# logger3.net
KiCad netlist of a schematic drawn in EAGLE
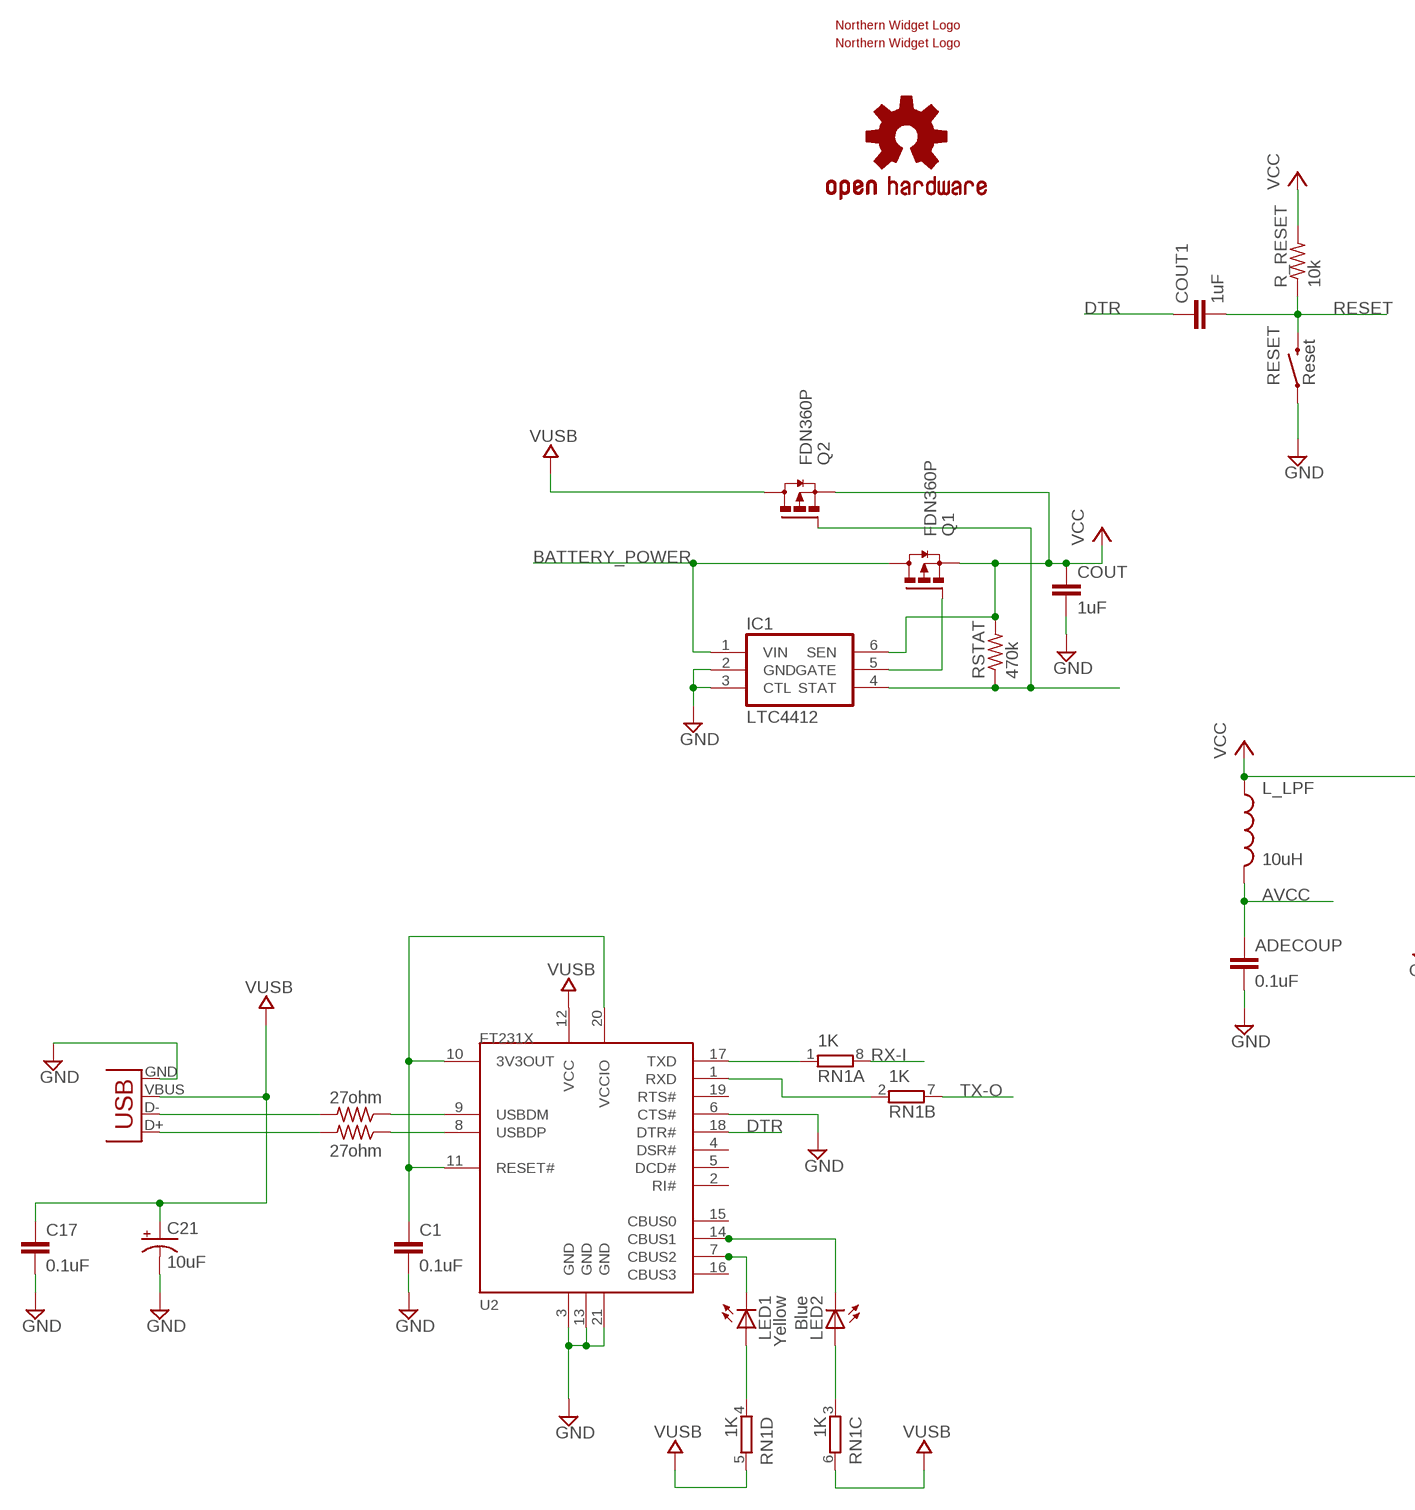
[diagram p0: schematic, sheet 1, part 1 of 2]
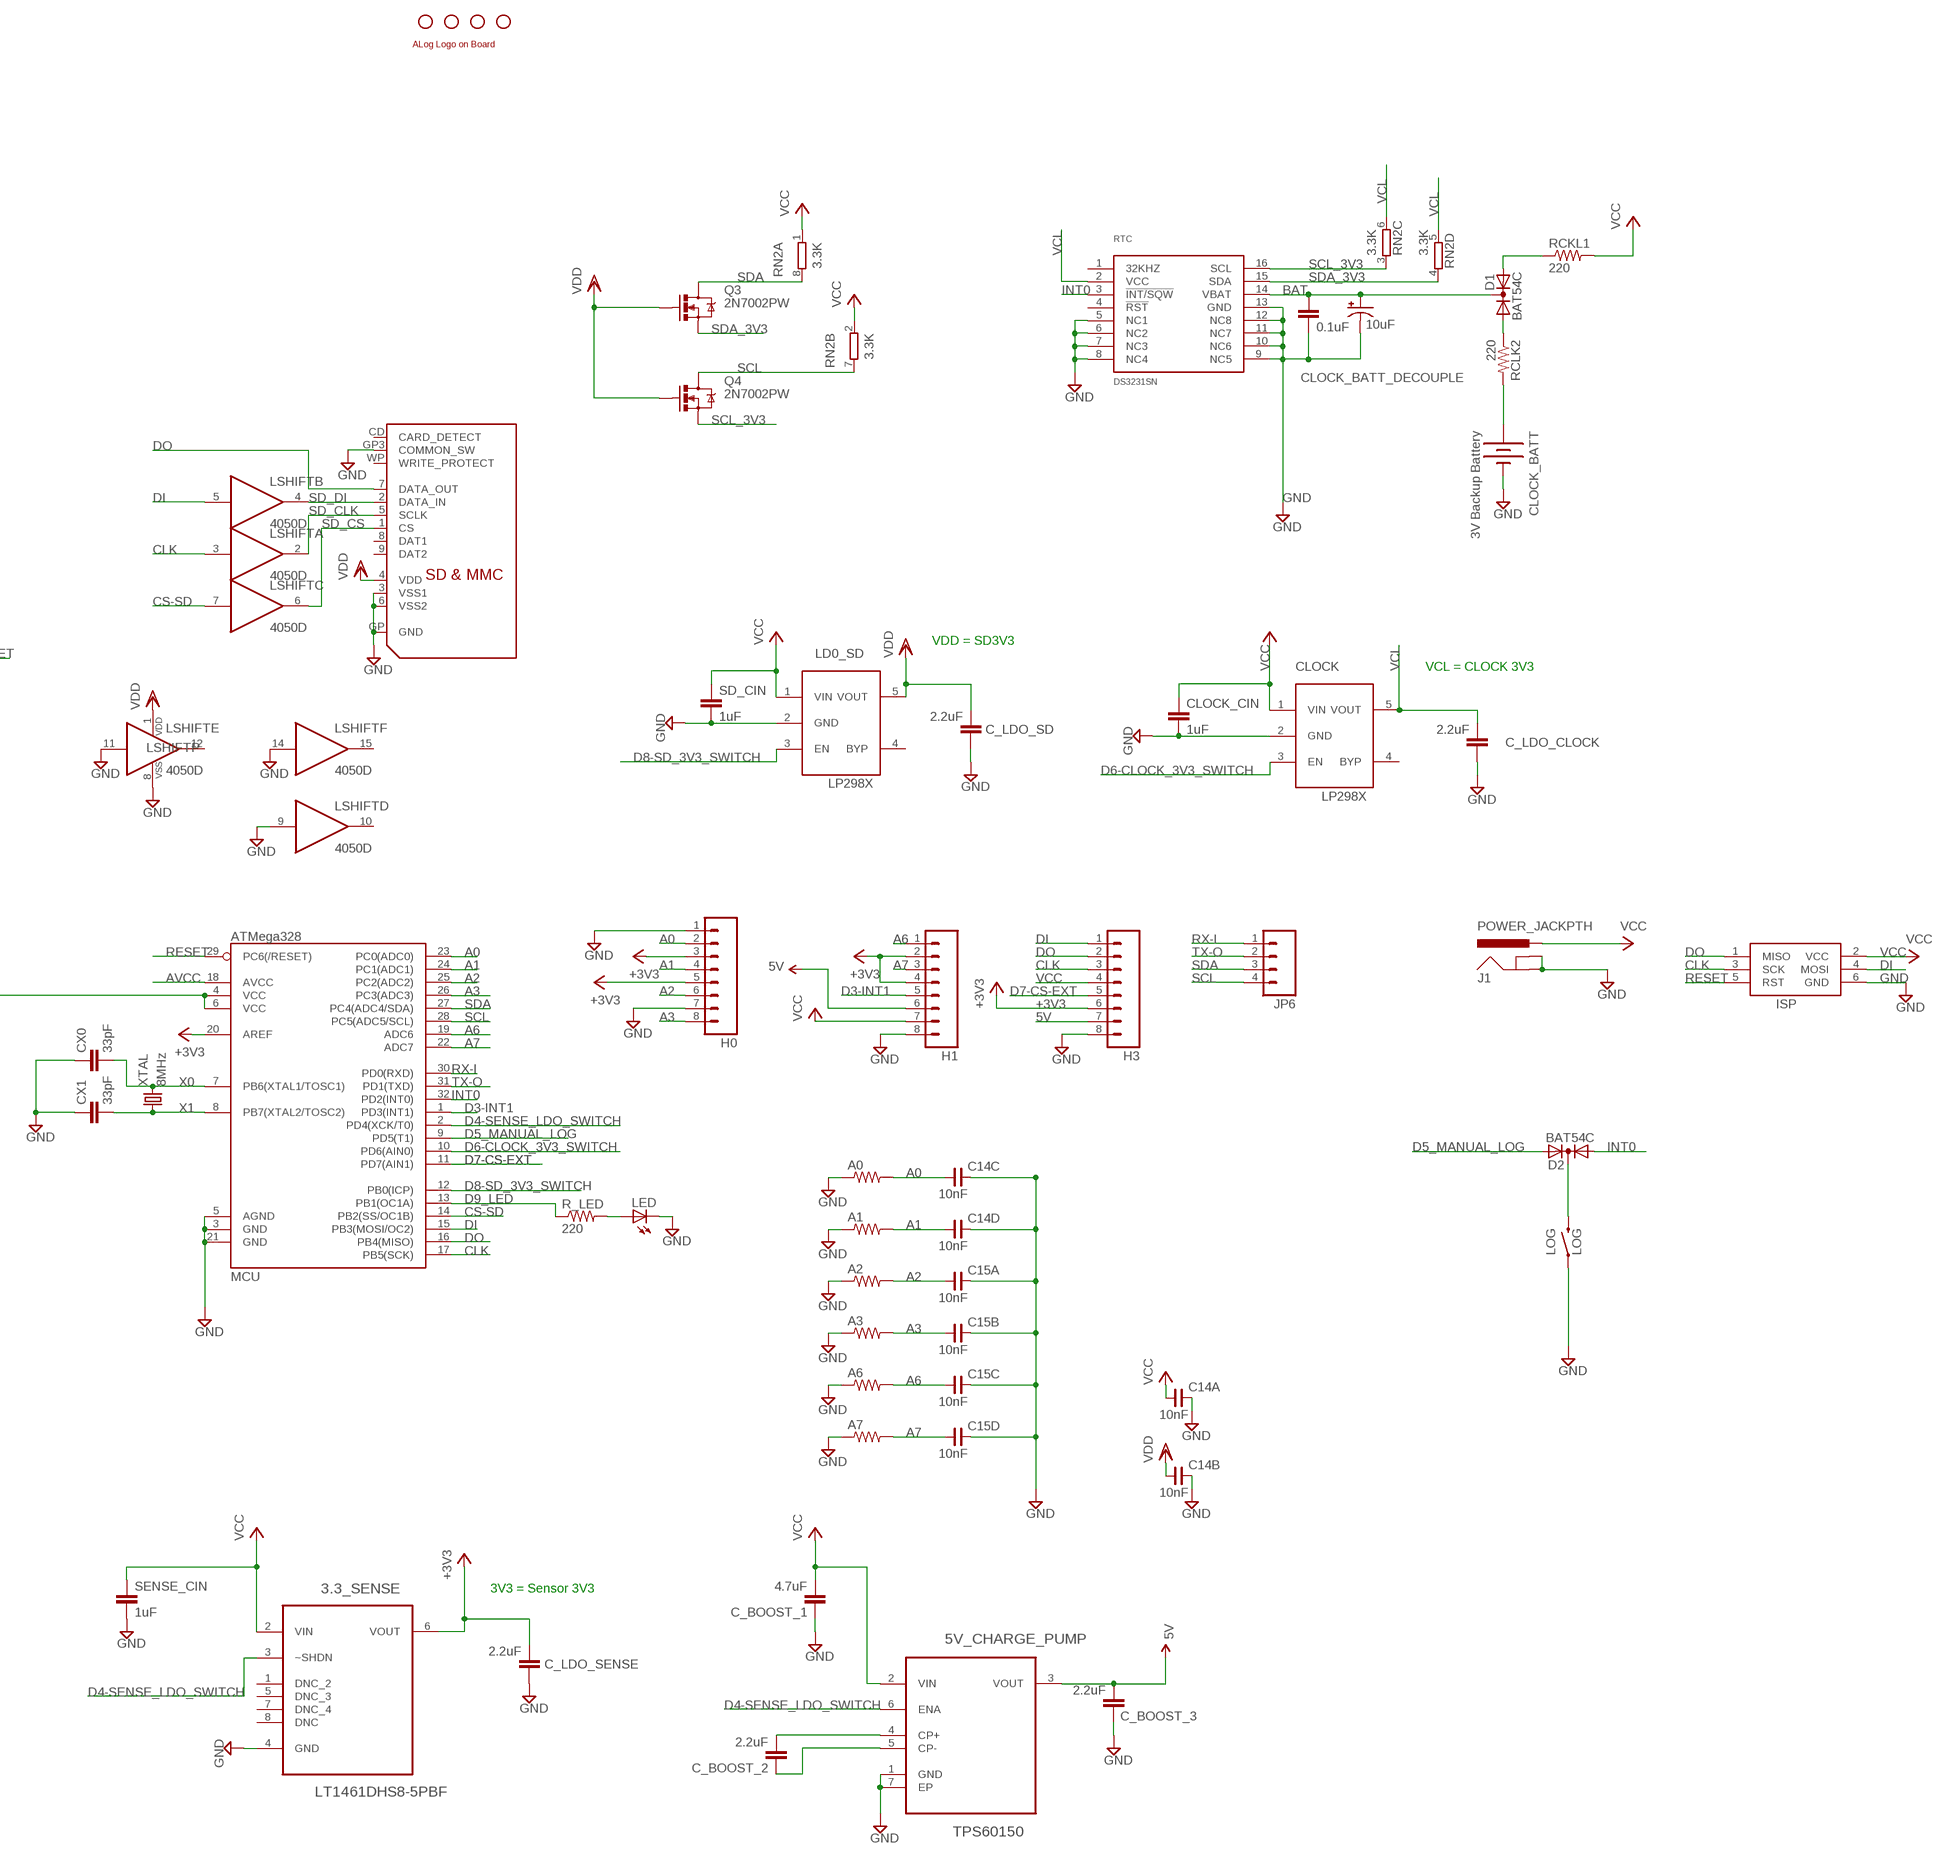
[diagram p1: schematic, sheet 1, part 2 of 2]

(export (version "E")
  (design (tool "Eeschema 10.0.6"))
  (components
    (comp (ref "3.3_SENSE")
      (value "LT1461DHS8-5PBF")
      (footprint "eagle-import:SOIC127P600X175-8N")
      (fields (field (name "MPN") "LT1461DHS8-5#PBF"))
      (libsource (lib "eagle-import") (part "LT1461DHS8-5PBF"))
    )
    (comp (ref "5V_CHARGE_PUMP")
      (value "TPS60150")
      (footprint "eagle-import:SON65P200X200X80-7N")
      (fields (field (name "MPN") "TPS60150DRVR"))
      (libsource (lib "eagle-import") (part "TPS60150DRVR"))
    )
    (comp (ref "A0")
      (value "R-US_0207/10")
      (footprint "eagle-import:0207_10")
      (libsource (lib "eagle-import") (part "resistor_R-US_0207/10"))
    )
    (comp (ref "A1")
      (value "R-US_0207/10")
      (footprint "eagle-import:0207_10")
      (libsource (lib "eagle-import") (part "resistor_R-US_0207/10"))
    )
    (comp (ref "A2")
      (value "R-US_0207/10")
      (footprint "eagle-import:0207_10")
      (libsource (lib "eagle-import") (part "resistor_R-US_0207/10"))
    )
    (comp (ref "A3")
      (value "R-US_0207/10")
      (footprint "eagle-import:0207_10")
      (libsource (lib "eagle-import") (part "resistor_R-US_0207/10"))
    )
    (comp (ref "A6")
      (value "R-US_0207/10")
      (footprint "eagle-import:0207_10")
      (libsource (lib "eagle-import") (part "resistor_R-US_0207/10"))
    )
    (comp (ref "A7")
      (value "R-US_0207/10")
      (footprint "eagle-import:0207_10")
      (libsource (lib "eagle-import") (part "resistor_R-US_0207/10"))
    )
    (comp (ref "ADECOUP")
      (value "0.1uF")
      (footprint "eagle-import:C0603")
      (libsource (lib "eagle-import") (part "resistor_C-EUC0603"))
    )
    (comp (ref "C1")
      (value "0.1uF")
      (footprint "eagle-import:C0603")
      (libsource (lib "eagle-import") (part "resistor_C-EUC0603"))
    )
    (comp (ref "C14")
      (value "10nF")
      (footprint "eagle-import:CECJ-1206")
      (libsource (lib "eagle-import") (part "CCA_ECJ-1206"))
    )
    (comp (ref "C15")
      (value "10nF")
      (footprint "eagle-import:CECJ-1206")
      (libsource (lib "eagle-import") (part "CCA_ECJ-1206"))
    )
    (comp (ref "C17")
      (value "0.1uF")
      (footprint "eagle-import:C0603")
      (libsource (lib "eagle-import") (part "resistor_C-EUC0603"))
    )
    (comp (ref "C21")
      (value "10uF")
      (footprint "eagle-import:EIA3216")
      (libsource (lib "eagle-import") (part "CAP_POL1206"))
    )
    (comp (ref "CLOCK")
      (value "LP2985")
      (footprint "eagle-import:SOT23-5L")
      (libsource (lib "eagle-import") (part "LP298XS"))
    )
    (comp (ref "CLOCK_BATT")
      (value "3V Backup Battery")
      (footprint "eagle-import:BATTCON_12MM_PTH")
      (libsource (lib "eagle-import") (part "BATTERY12PTH"))
    )
    (comp (ref "CLOCK_BATT_DECOUP")
      (value "0.1uF")
      (footprint "eagle-import:C0603")
      (libsource (lib "eagle-import") (part "C-EUC0603"))
    )
    (comp (ref "CLOCK_BATT_DECOUPLE")
      (value "10uF")
      (footprint "eagle-import:EIA3216")
      (libsource (lib "eagle-import") (part "CAP_POL1206"))
    )
    (comp (ref "CLOCK_CIN")
      (value "1uF")
      (footprint "eagle-import:C0603")
      (libsource (lib "eagle-import") (part "C-EUC0603"))
    )
    (comp (ref "COUT")
      (value "1uF")
      (footprint "eagle-import:C0603")
      (libsource (lib "eagle-import") (part "C-EUC0603"))
    )
    (comp (ref "COUT1")
      (value "1uF")
      (footprint "eagle-import:C0603")
      (libsource (lib "eagle-import") (part "C-EUC0603"))
    )
    (comp (ref "CX0")
      (value "33pF")
      (footprint "eagle-import:C0603")
      (libsource (lib "eagle-import") (part "resistor_C-EUC0603"))
    )
    (comp (ref "CX1")
      (value "33pF")
      (footprint "eagle-import:C0603")
      (libsource (lib "eagle-import") (part "resistor_C-EUC0603"))
    )
    (comp (ref "C_BOOST_1")
      (value "4.7uF")
      (footprint "eagle-import:C0603")
      (libsource (lib "eagle-import") (part "resistor_C-EUC0603"))
    )
    (comp (ref "C_BOOST_2")
      (value "2.2uF")
      (footprint "eagle-import:C0603")
      (libsource (lib "eagle-import") (part "resistor_C-EUC0603"))
    )
    (comp (ref "C_BOOST_3")
      (value "2.2uF")
      (footprint "eagle-import:C0603")
      (libsource (lib "eagle-import") (part "resistor_C-EUC0603"))
    )
    (comp (ref "C_LDO_CLOCK")
      (value "2.2uF")
      (footprint "eagle-import:C0603")
      (libsource (lib "eagle-import") (part "resistor_C-EUC0603"))
    )
    (comp (ref "C_LDO_SD")
      (value "2.2uF")
      (footprint "eagle-import:C0603")
      (libsource (lib "eagle-import") (part "resistor_C-EUC0603"))
    )
    (comp (ref "C_LDO_SENSE")
      (value "2.2uF")
      (footprint "eagle-import:C0603")
      (libsource (lib "eagle-import") (part "resistor_C-EUC0603"))
    )
    (comp (ref "D+")
      (value "27ohm")
      (footprint "eagle-import:R0603")
      (libsource (lib "eagle-import") (part "R-US_R0603"))
    )
    (comp (ref "D-")
      (value "27ohm")
      (footprint "eagle-import:R0603")
      (libsource (lib "eagle-import") (part "R-US_R0603"))
    )
    (comp (ref "D1")
      (value "BAT54C")
      (footprint "eagle-import:SOT23C")
      (libsource (lib "eagle-import") (part "DIODE_AC-CA_"))
    )
    (comp (ref "D2")
      (value "BAT54C")
      (footprint "eagle-import:SOT23C")
      (libsource (lib "eagle-import") (part "DIODE_AC-CA_"))
    )
    (comp (ref "H0")
      (value "M083.5MM-8")
      (footprint "eagle-import:SCREWTERMINAL-3.5MM-8")
      (libsource (lib "eagle-import") (part "M083.5MM-8"))
    )
    (comp (ref "H1")
      (value "M083.5MM-8")
      (footprint "eagle-import:SCREWTERMINAL-3.5MM-8")
      (libsource (lib "eagle-import") (part "M083.5MM-8"))
    )
    (comp (ref "H3")
      (value "M083.5MM-8")
      (footprint "eagle-import:SCREWTERMINAL-3.5MM-8")
      (libsource (lib "eagle-import") (part "M083.5MM-8"))
    )
    (comp (ref "IC1")
      (value "LTC4412")
      (footprint "eagle-import:TSOT23-6")
      (libsource (lib "eagle-import") (part "LTC4412S6E"))
    )
    (comp (ref "ISP")
      (value "AVRISP-6")
      (footprint "eagle-import:AVRISP")
      (libsource (lib "eagle-import") (part "AVRISP-6"))
    )
    (comp (ref "J1")
      (value "POWER_JACKPTH")
      (footprint "eagle-import:POWER_JACK_PTH")
      (libsource (lib "eagle-import") (part "POWER_JACKPTH"))
    )
    (comp (ref "JP1")
      (value "STAND-OFF")
      (footprint "eagle-import:STAND-OFF")
      (libsource (lib "eagle-import") (part "STAND-OFF"))
    )
    (comp (ref "JP2")
      (value "STAND-OFF")
      (footprint "eagle-import:STAND-OFF")
      (libsource (lib "eagle-import") (part "STAND-OFF"))
    )
    (comp (ref "JP3")
      (value "STAND-OFF")
      (footprint "eagle-import:STAND-OFF")
      (libsource (lib "eagle-import") (part "STAND-OFF"))
    )
    (comp (ref "JP4")
      (value "STAND-OFF")
      (footprint "eagle-import:STAND-OFF")
      (libsource (lib "eagle-import") (part "STAND-OFF"))
    )
    (comp (ref "JP5")
      (value "USB-B")
      (footprint "eagle-import:USB-B-PTH")
      (libsource (lib "eagle-import") (part "USBPTH"))
    )
    (comp (ref "JP6")
      (value "M04SCREW")
      (footprint "eagle-import:SCREWTERMINAL-3.5MM-4")
      (libsource (lib "eagle-import") (part "M04SCREW"))
    )
    (comp (ref "LD0_SD")
      (value "LP2985")
      (footprint "eagle-import:SOT23-5L")
      (libsource (lib "eagle-import") (part "LP298XS"))
    )
    (comp (ref "LED")
      (value "LED3MM")
      (footprint "eagle-import:LED3MM")
      (libsource (lib "eagle-import") (part "LED3MM"))
    )
    (comp (ref "LED1")
      (value "Yellow")
      (footprint "eagle-import:LED-0603")
      (libsource (lib "eagle-import") (part "SparkFun-LED_LED0603"))
    )
    (comp (ref "LED2")
      (value "Blue")
      (footprint "eagle-import:LED-0603")
      (libsource (lib "eagle-import") (part "SparkFun-LED_LED0603"))
    )
    (comp (ref "LOG")
      (value "LOG")
      (footprint "eagle-import:TACTILE-PTH")
      (libsource (lib "eagle-import") (part "SWITCH-MOMENTARY-2PTH"))
    )
    (comp (ref "LOGO1")
      (value "OSHW-LOGOM")
      (footprint "eagle-import:OSHW-LOGO-M")
      (libsource (lib "eagle-import") (part "OSHW-LOGOM"))
    )
    (comp (ref "LSHIFT")
      (value "4050D")
      (footprint "eagle-import:SO16")
      (libsource (lib "eagle-import") (part "4050D"))
    )
    (comp (ref "L_LPF")
      (value "10uH")
      (footprint "eagle-import:0805")
      (libsource (lib "eagle-import") (part "INDUCTOR0805"))
    )
    (comp (ref "MCU")
      (value "ATMega328")
      (footprint "eagle-import:TQFP32-08")
      (libsource (lib "eagle-import") (part "ATMEGA168"))
    )
    (comp (ref "Q1")
      (value "FDN360P")
      (footprint "eagle-import:SUPER-SOT3")
      (libsource (lib "eagle-import") (part "FDN360P"))
    )
    (comp (ref "Q2")
      (value "FDN360P")
      (footprint "eagle-import:SUPER-SOT3")
      (libsource (lib "eagle-import") (part "FDN360P"))
    )
    (comp (ref "Q3")
      (value "2N7002PW")
      (footprint "eagle-import:SOT323")
      (libsource (lib "eagle-import") (part "MOSFET-NCHANNELSOT323"))
    )
    (comp (ref "Q4")
      (value "2N7002PW")
      (footprint "eagle-import:SOT323")
      (libsource (lib "eagle-import") (part "MOSFET-NCHANNELSOT323"))
    )
    (comp (ref "RCKL1")
      (value "220")
      (footprint "eagle-import:R0603")
      (libsource (lib "eagle-import") (part "R-US_R0603"))
    )
    (comp (ref "RCLK2")
      (value "220")
      (footprint "eagle-import:R0603")
      (libsource (lib "eagle-import") (part "R-US_R0603"))
    )
    (comp (ref "RESET")
      (value "Reset")
      (footprint "eagle-import:TACTILE-PTH")
      (libsource (lib "eagle-import") (part "SWITCH-MOMENTARY-2PTH"))
    )
    (comp (ref "RN1")
      (value "1K")
      (footprint "eagle-import:0603-ARC")
      (libsource (lib "eagle-import") (part "4R-N0603-ARC"))
    )
    (comp (ref "RN2")
      (value "3.3K")
      (footprint "eagle-import:0603-ARC")
      (libsource (lib "eagle-import") (part "4R-N0603-ARC"))
    )
    (comp (ref "RSTAT")
      (value "470k")
      (footprint "eagle-import:R0603")
      (libsource (lib "eagle-import") (part "R-US_R0603"))
    )
    (comp (ref "RTC")
      (value "DS3231SN")
      (footprint "eagle-import:SO16W")
      (libsource (lib "eagle-import") (part "DS3231SN"))
    )
    (comp (ref "R_LED")
      (value "220")
      (footprint "eagle-import:R0603")
      (libsource (lib "eagle-import") (part "resistor_R-US_R0603"))
    )
    (comp (ref "R_RESET")
      (value "10k")
      (footprint "eagle-import:R0603")
      (libsource (lib "eagle-import") (part "R-US_R0603"))
    )
    (comp (ref "SD")
      (value "SDMMC06132")
      (footprint "eagle-import:06132")
      (libsource (lib "eagle-import") (part "SDMMC06132"))
    )
    (comp (ref "SD_CIN")
      (value "1uF")
      (footprint "eagle-import:C0603")
      (libsource (lib "eagle-import") (part "C-EUC0603"))
    )
    (comp (ref "SENSE_CIN")
      (value "1uF")
      (footprint "eagle-import:C0603")
      (libsource (lib "eagle-import") (part "C-EUC0603"))
    )
    (comp (ref "U$1")
      (value "NWLOGO")
      (footprint "eagle-import:NWLOGO")
      (libsource (lib "eagle-import") (part "NWLOGO"))
    )
    (comp (ref "U$2")
      (value "ALOG_LOGO_V1_5.5MM")
      (footprint "eagle-import:ALOG_LOGO_V1_SMALL")
      (libsource (lib "eagle-import") (part "ALOG_LOGO_V1_5.5MM"))
    )
    (comp (ref "U$3")
      (value "NWLOGO_MED")
      (footprint "eagle-import:NWLOGO_MED")
      (libsource (lib "eagle-import") (part "NWLOGO_MED"))
    )
    (comp (ref "U2")
      (value "FT231X-Q")
      (footprint "eagle-import:QFN20")
      (libsource (lib "eagle-import") (part "FT231X-Q"))
    )
    (comp (ref "XTAL")
      (value "8MHz")
      (footprint "eagle-import:HC49U-V")
      (libsource (lib "eagle-import") (part "CRYSTALHC49UV"))
    )
  )
  (nets
    (net (code "1") (name "+3V3") (class "Default")
      (node (ref "3.3_SENSE") (pin "6") (pinfunction "VOUT_6") (pintype "output"))
      (node (ref "C_LDO_SENSE") (pin "2") (pinfunction "2_2") (pintype "passive"))
      (node (ref "H0") (pin "3") (pinfunction "3_3") (pintype "passive"))
      (node (ref "H0") (pin "5") (pinfunction "5_5") (pintype "passive"))
      (node (ref "H1") (pin "2") (pinfunction "2_2") (pintype "passive"))
      (node (ref "H1") (pin "4") (pinfunction "4_4") (pintype "passive"))
      (node (ref "H3") (pin "6") (pinfunction "6_6") (pintype "passive"))
      (node (ref "MCU") (pin "20") (pinfunction "AREF_20") (pintype "bidirectional"))
    )
    (net (code "2") (name "/A0") (class "Default")
      (node (ref "A0") (pin "2") (pinfunction "2_2") (pintype "passive"))
      (node (ref "C14") (pin "C1") (pinfunction "1_C1") (pintype "passive"))
      (node (ref "H0") (pin "2") (pinfunction "2_2") (pintype "passive"))
      (node (ref "MCU") (pin "23") (pinfunction "PC0(ADC0)_23") (pintype "bidirectional"))
    )
    (net (code "3") (name "/A1") (class "Default")
      (node (ref "A1") (pin "2") (pinfunction "2_2") (pintype "passive"))
      (node (ref "C14") (pin "D1") (pinfunction "1_D1") (pintype "passive"))
      (node (ref "H0") (pin "4") (pinfunction "4_4") (pintype "passive"))
      (node (ref "MCU") (pin "24") (pinfunction "PC1(ADC1)_24") (pintype "bidirectional"))
    )
    (net (code "4") (name "/A2") (class "Default")
      (node (ref "A2") (pin "2") (pinfunction "2_2") (pintype "passive"))
      (node (ref "C15") (pin "A1") (pinfunction "1_A1") (pintype "passive"))
      (node (ref "H0") (pin "6") (pinfunction "6_6") (pintype "passive"))
      (node (ref "MCU") (pin "25") (pinfunction "PC2(ADC2)_25") (pintype "bidirectional"))
    )
    (net (code "5") (name "/A3") (class "Default")
      (node (ref "A3") (pin "2") (pinfunction "2_2") (pintype "passive"))
      (node (ref "C15") (pin "B1") (pinfunction "1_B1") (pintype "passive"))
      (node (ref "H0") (pin "8") (pinfunction "8_8") (pintype "passive"))
      (node (ref "MCU") (pin "26") (pinfunction "PC3(ADC3)_26") (pintype "bidirectional"))
    )
    (net (code "6") (name "/A6") (class "Default")
      (node (ref "A6") (pin "2") (pinfunction "2_2") (pintype "passive"))
      (node (ref "C15") (pin "C1") (pinfunction "1_C1") (pintype "passive"))
      (node (ref "H1") (pin "1") (pinfunction "1_1") (pintype "passive"))
      (node (ref "MCU") (pin "19") (pinfunction "ADC6_19") (pintype "bidirectional"))
    )
    (net (code "7") (name "/A7") (class "Default")
      (node (ref "A7") (pin "2") (pinfunction "2_2") (pintype "passive"))
      (node (ref "C15") (pin "D1") (pinfunction "1_D1") (pintype "passive"))
      (node (ref "H1") (pin "3") (pinfunction "3_3") (pintype "passive"))
      (node (ref "MCU") (pin "22") (pinfunction "ADC7_22") (pintype "bidirectional"))
    )
    (net (code "8") (name "/AVCC") (class "Default")
      (node (ref "ADECOUP") (pin "1") (pinfunction "1_1") (pintype "passive"))
      (node (ref "L_LPF") (pin "2") (pinfunction "2_2") (pintype "passive"))
      (node (ref "MCU") (pin "18") (pinfunction "AVCC_18") (pintype "bidirectional"))
    )
    (net (code "9") (name "/BAT") (class "Default")
      (node (ref "CLOCK_BATT_DECOUP") (pin "1") (pinfunction "1_1") (pintype "passive"))
      (node (ref "CLOCK_BATT_DECOUPLE") (pin "A") (pinfunction "+_A") (pintype "passive"))
      (node (ref "D1") (pin "3") (pinfunction "K_3") (pintype "passive"))
      (node (ref "RTC") (pin "14") (pinfunction "VBAT_14") (pintype "bidirectional"))
    )
    (net (code "10") (name "/BATTERY_POWER") (class "Default")
      (node (ref "IC1") (pin "1") (pinfunction "VIN_1") (pintype "input"))
      (node (ref "Q1") (pin "3") (pinfunction "D_3") (pintype "passive"))
    )
    (net (code "11") (name "/CLK") (class "Default")
      (node (ref "H3") (pin "3") (pinfunction "3_3") (pintype "passive"))
      (node (ref "ISP") (pin "3") (pinfunction "SCK_3") (pintype "output"))
      (node (ref "LSHIFT") (pin "3") (pinfunction "I_3") (pintype "input"))
      (node (ref "MCU") (pin "17") (pinfunction "PB5(SCK)_17") (pintype "bidirectional"))
    )
    (net (code "12") (name "/CS-SD") (class "Default")
      (node (ref "LSHIFT") (pin "7") (pinfunction "I_7") (pintype "input"))
      (node (ref "MCU") (pin "14") (pinfunction "PB2(SS/OC1B)_14") (pintype "bidirectional"))
    )
    (net (code "13") (name "/D3-INT1") (class "Default")
      (node (ref "H1") (pin "5") (pinfunction "5_5") (pintype "passive"))
      (node (ref "MCU") (pin "1") (pinfunction "PD3(INT1)_1") (pintype "bidirectional"))
    )
    (net (code "14") (name "/D4-SENSE_LDO_SWITCH") (class "Default")
      (node (ref "3.3_SENSE") (pin "3") (pinfunction "~{SHDN}_3") (pintype "input"))
      (node (ref "5V_CHARGE_PUMP") (pin "6") (pinfunction "ENA_6") (pintype "input"))
      (node (ref "MCU") (pin "2") (pinfunction "PD4(XCK/T0)_2") (pintype "bidirectional"))
    )
    (net (code "15") (name "/D5_MANUAL_LOG") (class "Default")
      (node (ref "D2") (pin "2") (pinfunction "A2_2") (pintype "passive"))
      (node (ref "MCU") (pin "9") (pinfunction "PD5(T1)_9") (pintype "bidirectional"))
    )
    (net (code "16") (name "/D6-CLOCK_3V3_SWITCH") (class "Default")
      (node (ref "CLOCK") (pin "3") (pinfunction "EN_3") (pintype "bidirectional"))
      (node (ref "MCU") (pin "10") (pinfunction "PD6(AIN0)_10") (pintype "bidirectional"))
    )
    (net (code "17") (name "/D7-CS-EXT") (class "Default")
      (node (ref "H3") (pin "5") (pinfunction "5_5") (pintype "passive"))
      (node (ref "MCU") (pin "11") (pinfunction "PD7(AIN1)_11") (pintype "bidirectional"))
    )
    (net (code "18") (name "/D8-SD_3V3_SWITCH") (class "Default")
      (node (ref "LD0_SD") (pin "3") (pinfunction "EN_3") (pintype "bidirectional"))
      (node (ref "MCU") (pin "12") (pinfunction "PB0(ICP)_12") (pintype "bidirectional"))
    )
    (net (code "19") (name "/D9_LED") (class "Default")
      (node (ref "MCU") (pin "13") (pinfunction "PB1(OC1A)_13") (pintype "bidirectional"))
      (node (ref "R_LED") (pin "1") (pinfunction "1_1") (pintype "passive"))
    )
    (net (code "20") (name "/DI") (class "Default")
      (node (ref "H3") (pin "1") (pinfunction "1_1") (pintype "passive"))
      (node (ref "ISP") (pin "4") (pinfunction "MOSI_4") (pintype "output"))
      (node (ref "LSHIFT") (pin "5") (pinfunction "I_5") (pintype "input"))
      (node (ref "MCU") (pin "15") (pinfunction "PB3(MOSI/OC2)_15") (pintype "bidirectional"))
    )
    (net (code "21") (name "/DO") (class "Default")
      (node (ref "H3") (pin "2") (pinfunction "2_2") (pintype "passive"))
      (node (ref "ISP") (pin "1") (pinfunction "MISO_1") (pintype "input"))
      (node (ref "MCU") (pin "16") (pinfunction "PB4(MISO)_16") (pintype "bidirectional"))
      (node (ref "SD") (pin "7") (pinfunction "DATA_OUT_7") (pintype "output"))
    )
    (net (code "22") (name "/DTR") (class "Default")
      (node (ref "COUT1") (pin "1") (pinfunction "1_1") (pintype "passive"))
      (node (ref "U2") (pin "18") (pinfunction "DTR#_18") (pintype "bidirectional"))
    )
    (net (code "23") (name "/INT0") (class "Default")
      (node (ref "D2") (pin "1") (pinfunction "A1_1") (pintype "passive"))
      (node (ref "MCU") (pin "32") (pinfunction "PD2(INT0)_32") (pintype "bidirectional"))
      (node (ref "RTC") (pin "3") (pinfunction "~{INT/SQW}_3") (pintype "bidirectional"))
    )
    (net (code "24") (name "/RESET") (class "Default")
      (node (ref "COUT1") (pin "2") (pinfunction "2_2") (pintype "passive"))
      (node (ref "ISP") (pin "5") (pinfunction "RST_5") (pintype "output"))
      (node (ref "MCU") (pin "29") (pinfunction "PC6(/RESET)_29") (pintype "bidirectional"))
      (node (ref "RESET") (pin "3") (pinfunction "2_3") (pintype "passive"))
      (node (ref "R_RESET") (pin "1") (pinfunction "1_1") (pintype "passive"))
    )
    (net (code "25") (name "/RX-I") (class "Default")
      (node (ref "JP6") (pin "1") (pinfunction "1_1") (pintype "passive"))
      (node (ref "MCU") (pin "30") (pinfunction "PD0(RXD)_30") (pintype "bidirectional"))
      (node (ref "RN1") (pin "8") (pinfunction "2_8") (pintype "passive"))
    )
    (net (code "26") (name "/SCL") (class "Default")
      (node (ref "JP6") (pin "4") (pinfunction "4_4") (pintype "passive"))
      (node (ref "MCU") (pin "28") (pinfunction "PC5(ADC5/SCL)_28") (pintype "bidirectional"))
      (node (ref "Q4") (pin "3") (pinfunction "D_3") (pintype "passive"))
      (node (ref "RN2") (pin "7") (pinfunction "2_7") (pintype "passive"))
    )
    (net (code "27") (name "/SCL_3V3") (class "Default")
      (node (ref "Q4") (pin "2") (pinfunction "S_2") (pintype "passive"))
      (node (ref "RN2") (pin "3") (pinfunction "1_3") (pintype "passive"))
      (node (ref "RTC") (pin "16") (pinfunction "SCL_16") (pintype "bidirectional"))
    )
    (net (code "28") (name "/SDA") (class "Default")
      (node (ref "JP6") (pin "3") (pinfunction "3_3") (pintype "passive"))
      (node (ref "MCU") (pin "27") (pinfunction "PC4(ADC4/SDA)_27") (pintype "bidirectional"))
      (node (ref "Q3") (pin "3") (pinfunction "D_3") (pintype "passive"))
      (node (ref "RN2") (pin "8") (pinfunction "2_8") (pintype "passive"))
    )
    (net (code "29") (name "/SDA_3V3") (class "Default")
      (node (ref "Q3") (pin "2") (pinfunction "S_2") (pintype "passive"))
      (node (ref "RN2") (pin "4") (pinfunction "1_4") (pintype "passive"))
      (node (ref "RTC") (pin "15") (pinfunction "SDA_15") (pintype "bidirectional"))
    )
    (net (code "30") (name "/SD_CLK") (class "Default")
      (node (ref "LSHIFT") (pin "2") (pinfunction "O_2") (pintype "output"))
      (node (ref "SD") (pin "5") (pinfunction "SCLK_5") (pintype "input"))
    )
    (net (code "31") (name "/SD_CS") (class "Default")
      (node (ref "LSHIFT") (pin "6") (pinfunction "O_6") (pintype "output"))
      (node (ref "SD") (pin "1") (pinfunction "CS_1") (pintype "input"))
    )
    (net (code "32") (name "/SD_DI") (class "Default")
      (node (ref "LSHIFT") (pin "4") (pinfunction "O_4") (pintype "output"))
      (node (ref "SD") (pin "2") (pinfunction "DATA_IN_2") (pintype "input"))
    )
    (net (code "33") (name "/TX-O") (class "Default")
      (node (ref "JP6") (pin "2") (pinfunction "2_2") (pintype "passive"))
      (node (ref "MCU") (pin "31") (pinfunction "PD1(TXD)_31") (pintype "bidirectional"))
      (node (ref "RN1") (pin "7") (pinfunction "2_7") (pintype "passive"))
    )
    (net (code "34") (name "/VCL") (class "Default")
      (node (ref "CLOCK") (pin "5") (pinfunction "VOUT_5") (pintype "bidirectional"))
      (node (ref "C_LDO_CLOCK") (pin "2") (pinfunction "2_2") (pintype "passive"))
      (node (ref "RN2") (pin "5") (pinfunction "2_5") (pintype "passive"))
      (node (ref "RN2") (pin "6") (pinfunction "2_6") (pintype "passive"))
      (node (ref "RTC") (pin "2") (pinfunction "VCC_2") (pintype "bidirectional"))
    )
    (net (code "35") (name "/X0") (class "Default")
      (node (ref "CX0") (pin "2") (pinfunction "2_2") (pintype "passive"))
      (node (ref "MCU") (pin "7") (pinfunction "PB6(XTAL1/TOSC1)_7") (pintype "bidirectional"))
      (node (ref "XTAL") (pin "2") (pinfunction "2_2") (pintype "passive"))
    )
    (net (code "36") (name "/X1") (class "Default")
      (node (ref "CX1") (pin "2") (pinfunction "2_2") (pintype "passive"))
      (node (ref "MCU") (pin "8") (pinfunction "PB7(XTAL2/TOSC2)_8") (pintype "bidirectional"))
      (node (ref "XTAL") (pin "1") (pinfunction "1_1") (pintype "passive"))
    )
    (net (code "37") (name "5V") (class "Default")
      (node (ref "5V_CHARGE_PUMP") (pin "3") (pinfunction "VOUT_3") (pintype "output"))
      (node (ref "C_BOOST_3") (pin "2") (pinfunction "2_2") (pintype "passive"))
      (node (ref "H1") (pin "6") (pinfunction "6_6") (pintype "passive"))
      (node (ref "H3") (pin "7") (pinfunction "7_7") (pintype "passive"))
    )
    (net (code "38") (name "GND") (class "Default")
      (node (ref "3.3_SENSE") (pin "4") (pinfunction "GND_4") (pintype "passive"))
      (node (ref "5V_CHARGE_PUMP") (pin "1") (pinfunction "GND_1") (pintype "passive"))
      (node (ref "5V_CHARGE_PUMP") (pin "7") (pinfunction "EP_7") (pintype "passive"))
      (node (ref "A0") (pin "1") (pinfunction "1_1") (pintype "passive"))
      (node (ref "A1") (pin "1") (pinfunction "1_1") (pintype "passive"))
      (node (ref "A2") (pin "1") (pinfunction "1_1") (pintype "passive"))
      (node (ref "A3") (pin "1") (pinfunction "1_1") (pintype "passive"))
      (node (ref "A6") (pin "1") (pinfunction "1_1") (pintype "passive"))
      (node (ref "A7") (pin "1") (pinfunction "1_1") (pintype "passive"))
      (node (ref "ADECOUP") (pin "2") (pinfunction "2_2") (pintype "passive"))
      (node (ref "C1") (pin "2") (pinfunction "2_2") (pintype "passive"))
      (node (ref "C14") (pin "A2") (pinfunction "2_A2") (pintype "passive"))
      (node (ref "C14") (pin "B2") (pinfunction "2_B2") (pintype "passive"))
      (node (ref "C14") (pin "C2") (pinfunction "2_C2") (pintype "passive"))
      (node (ref "C14") (pin "D2") (pinfunction "2_D2") (pintype "passive"))
      (node (ref "C15") (pin "A2") (pinfunction "2_A2") (pintype "passive"))
      (node (ref "C15") (pin "B2") (pinfunction "2_B2") (pintype "passive"))
      (node (ref "C15") (pin "C2") (pinfunction "2_C2") (pintype "passive"))
      (node (ref "C15") (pin "D2") (pinfunction "2_D2") (pintype "passive"))
      (node (ref "C17") (pin "2") (pinfunction "2_2") (pintype "passive"))
      (node (ref "C21") (pin "C") (pinfunction "-_C") (pintype "passive"))
      (node (ref "CLOCK") (pin "2") (pinfunction "GND_2") (pintype "bidirectional"))
      (node (ref "CLOCK_BATT") (pin "GND") (pinfunction "-_GND") (pintype "power_in"))
      (node (ref "CLOCK_BATT_DECOUP") (pin "2") (pinfunction "2_2") (pintype "passive"))
      (node (ref "CLOCK_BATT_DECOUPLE") (pin "C") (pinfunction "-_C") (pintype "passive"))
      (node (ref "CLOCK_CIN") (pin "2") (pinfunction "2_2") (pintype "passive"))
      (node (ref "COUT") (pin "2") (pinfunction "2_2") (pintype "passive"))
      (node (ref "CX0") (pin "1") (pinfunction "1_1") (pintype "passive"))
      (node (ref "CX1") (pin "1") (pinfunction "1_1") (pintype "passive"))
      (node (ref "C_BOOST_1") (pin "1") (pinfunction "1_1") (pintype "passive"))
      (node (ref "C_BOOST_3") (pin "1") (pinfunction "1_1") (pintype "passive"))
      (node (ref "C_LDO_CLOCK") (pin "1") (pinfunction "1_1") (pintype "passive"))
      (node (ref "C_LDO_SD") (pin "1") (pinfunction "1_1") (pintype "passive"))
      (node (ref "C_LDO_SENSE") (pin "1") (pinfunction "1_1") (pintype "passive"))
      (node (ref "H0") (pin "1") (pinfunction "1_1") (pintype "passive"))
      (node (ref "H0") (pin "7") (pinfunction "7_7") (pintype "passive"))
      (node (ref "H1") (pin "8") (pinfunction "8_8") (pintype "passive"))
      (node (ref "H3") (pin "8") (pinfunction "8_8") (pintype "passive"))
      (node (ref "IC1") (pin "2") (pinfunction "GND_2") (pintype "passive"))
      (node (ref "IC1") (pin "3") (pinfunction "CTL_3") (pintype "input"))
      (node (ref "ISP") (pin "6") (pinfunction "GND_6") (pintype "power_in"))
      (node (ref "J1") (pin "GND") (pinfunction "GND_GND") (pintype "bidirectional"))
      (node (ref "J1") (pin "GNDBREAK") (pinfunction "GNDBREAK_GNDBREAK") (pintype "bidirectional"))
      (node (ref "JP5") (pin "GND") (pinfunction "GND_GND") (pintype "bidirectional"))
      (node (ref "LD0_SD") (pin "2") (pinfunction "GND_2") (pintype "bidirectional"))
      (node (ref "LED") (pin "K") (pinfunction "C_K") (pintype "passive"))
      (node (ref "LOG") (pin "1") (pinfunction "1_1") (pintype "passive"))
      (node (ref "LSHIFT") (pin "11") (pinfunction "I_11") (pintype "input"))
      (node (ref "LSHIFT") (pin "14") (pinfunction "I_14") (pintype "input"))
      (node (ref "LSHIFT") (pin "8") (pinfunction "VSS_8") (pintype "power_in"))
      (node (ref "LSHIFT") (pin "9") (pinfunction "I_9") (pintype "input"))
      (node (ref "MCU") (pin "21") (pinfunction "GND_21") (pintype "bidirectional"))
      (node (ref "MCU") (pin "3") (pinfunction "GND_3") (pintype "bidirectional"))
      (node (ref "MCU") (pin "5") (pinfunction "AGND_5") (pintype "bidirectional"))
      (node (ref "RESET") (pin "1") (pinfunction "1_1") (pintype "passive"))
      (node (ref "RTC") (pin "10") (pinfunction "NC6_10") (pintype "bidirectional"))
      (node (ref "RTC") (pin "11") (pinfunction "NC7_11") (pintype "bidirectional"))
      (node (ref "RTC") (pin "12") (pinfunction "NC8_12") (pintype "bidirectional"))
      (node (ref "RTC") (pin "13") (pinfunction "GND_13") (pintype "bidirectional"))
      (node (ref "RTC") (pin "5") (pinfunction "NC1_5") (pintype "bidirectional"))
      (node (ref "RTC") (pin "6") (pinfunction "NC2_6") (pintype "bidirectional"))
      (node (ref "RTC") (pin "7") (pinfunction "NC3_7") (pintype "bidirectional"))
      (node (ref "RTC") (pin "8") (pinfunction "NC4_8") (pintype "bidirectional"))
      (node (ref "RTC") (pin "9") (pinfunction "NC5_9") (pintype "bidirectional"))
      (node (ref "SD") (pin "3") (pinfunction "VSS1_3") (pintype "power_in"))
      (node (ref "SD") (pin "6") (pinfunction "VSS2_6") (pintype "power_in"))
      (node (ref "SD") (pin "GP") (pinfunction "GND_GP") (pintype "power_in"))
      (node (ref "SD") (pin "GP3") (pinfunction "COMMON_SW_GP3") (pintype "passive"))
      (node (ref "SD_CIN") (pin "2") (pinfunction "2_2") (pintype "passive"))
      (node (ref "SENSE_CIN") (pin "2") (pinfunction "2_2") (pintype "passive"))
      (node (ref "U2") (pin "13") (pinfunction "GND_13") (pintype "bidirectional"))
      (node (ref "U2") (pin "21") (pinfunction "GND_21") (pintype "bidirectional"))
      (node (ref "U2") (pin "3") (pinfunction "GND_3") (pintype "bidirectional"))
      (node (ref "U2") (pin "6") (pinfunction "CTS#_6") (pintype "bidirectional"))
    )
    (net (code "39") (name "Net-(5V_CHARGE_PUMP-CP+)") (class "Default")
      (node (ref "5V_CHARGE_PUMP") (pin "4") (pinfunction "CP+_4") (pintype "passive"))
      (node (ref "C_BOOST_2") (pin "2") (pinfunction "2_2") (pintype "passive"))
    )
    (net (code "40") (name "Net-(5V_CHARGE_PUMP-CP-)") (class "Default")
      (node (ref "5V_CHARGE_PUMP") (pin "5") (pinfunction "CP-_5") (pintype "passive"))
      (node (ref "C_BOOST_2") (pin "1") (pinfunction "1_1") (pintype "passive"))
    )
    (net (code "41") (name "Net-(CLOCK_BATT-+)") (class "Default")
      (node (ref "CLOCK_BATT") (pin "VCC@1") (pinfunction "+_VCC@1") (pintype "power_in"))
      (node (ref "RCLK2") (pin "2") (pinfunction "2_2") (pintype "passive"))
    )
    (net (code "42") (name "Net-(D+-Pad2)") (class "Default")
      (node (ref "D+") (pin "2") (pinfunction "2_2") (pintype "passive"))
      (node (ref "JP5") (pin "D+") (pinfunction "D+_D+") (pintype "bidirectional"))
    )
    (net (code "43") (name "Net-(D--Pad2)") (class "Default")
      (node (ref "D-") (pin "2") (pinfunction "2_2") (pintype "passive"))
      (node (ref "JP5") (pin "D-") (pinfunction "D-_D-") (pintype "bidirectional"))
    )
    (net (code "44") (name "Net-(D1-A1)") (class "Default")
      (node (ref "D1") (pin "1") (pinfunction "A1_1") (pintype "passive"))
      (node (ref "RCLK2") (pin "1") (pinfunction "1_1") (pintype "passive"))
    )
    (net (code "45") (name "Net-(D1-A2)") (class "Default")
      (node (ref "D1") (pin "2") (pinfunction "A2_2") (pintype "passive"))
      (node (ref "RCKL1") (pin "1") (pinfunction "1_1") (pintype "passive"))
    )
    (net (code "46") (name "Net-(D2-K)") (class "Default")
      (node (ref "D2") (pin "3") (pinfunction "K_3") (pintype "passive"))
      (node (ref "LOG") (pin "3") (pinfunction "2_3") (pintype "passive"))
    )
    (net (code "47") (name "Net-(IC1-GATE)") (class "Default")
      (node (ref "IC1") (pin "5") (pinfunction "GATE_5") (pintype "output"))
      (node (ref "Q1") (pin "1") (pinfunction "G_1") (pintype "passive"))
    )
    (net (code "48") (name "Net-(IC1-STAT)") (class "Default")
      (node (ref "IC1") (pin "4") (pinfunction "STAT_4") (pintype "open_collector"))
      (node (ref "Q2") (pin "1") (pinfunction "G_1") (pintype "passive"))
      (node (ref "RSTAT") (pin "1") (pinfunction "1_1") (pintype "passive"))
    )
    (net (code "49") (name "Net-(LED-PadA)") (class "Default")
      (node (ref "LED") (pin "A") (pinfunction "A_A") (pintype "passive"))
      (node (ref "R_LED") (pin "2") (pinfunction "2_2") (pintype "passive"))
    )
    (net (code "50") (name "Net-(RN1B-1)") (class "Default")
      (node (ref "RN1") (pin "2") (pinfunction "1_2") (pintype "passive"))
      (node (ref "U2") (pin "1") (pinfunction "RXD_1") (pintype "bidirectional"))
    )
    (net (code "51") (name "Net-(RN1C-1)") (class "Default")
      (node (ref "LED2") (pin "A") (pinfunction "A_A") (pintype "passive"))
      (node (ref "RN1") (pin "3") (pinfunction "1_3") (pintype "passive"))
    )
    (net (code "52") (name "Net-(RN1D-1)") (class "Default")
      (node (ref "LED1") (pin "A") (pinfunction "A_A") (pintype "passive"))
      (node (ref "RN1") (pin "4") (pinfunction "1_4") (pintype "passive"))
    )
    (net (code "53") (name "Net-(U2-3V3OUT)") (class "Default")
      (node (ref "C1") (pin "1") (pinfunction "1_1") (pintype "passive"))
      (node (ref "U2") (pin "10") (pinfunction "3V3OUT_10") (pintype "bidirectional"))
      (node (ref "U2") (pin "11") (pinfunction "RESET#_11") (pintype "bidirectional"))
      (node (ref "U2") (pin "20") (pinfunction "VCCIO_20") (pintype "bidirectional"))
    )
    (net (code "54") (name "Net-(U2-CBUS1)") (class "Default")
      (node (ref "LED2") (pin "C") (pinfunction "C_C") (pintype "passive"))
      (node (ref "U2") (pin "14") (pinfunction "CBUS1_14") (pintype "bidirectional"))
    )
    (net (code "55") (name "Net-(U2-CBUS2)") (class "Default")
      (node (ref "LED1") (pin "C") (pinfunction "C_C") (pintype "passive"))
      (node (ref "U2") (pin "7") (pinfunction "CBUS2_7") (pintype "bidirectional"))
    )
    (net (code "56") (name "Net-(U2-TXD)") (class "Default")
      (node (ref "RN1") (pin "1") (pinfunction "1_1") (pintype "passive"))
      (node (ref "U2") (pin "17") (pinfunction "TXD_17") (pintype "bidirectional"))
    )
    (net (code "57") (name "Net-(U2-USBDM)") (class "Default")
      (node (ref "D-") (pin "1") (pinfunction "1_1") (pintype "passive"))
      (node (ref "U2") (pin "9") (pinfunction "USBDM_9") (pintype "bidirectional"))
    )
    (net (code "58") (name "Net-(U2-USBDP)") (class "Default")
      (node (ref "D+") (pin "1") (pinfunction "1_1") (pintype "passive"))
      (node (ref "U2") (pin "8") (pinfunction "USBDP_8") (pintype "bidirectional"))
    )
    (net (code "59") (name "VCC") (class "Default")
      (node (ref "3.3_SENSE") (pin "2") (pinfunction "VIN_2") (pintype "power_in"))
      (node (ref "5V_CHARGE_PUMP") (pin "2") (pinfunction "VIN_2") (pintype "power_in"))
      (node (ref "C14") (pin "A1") (pinfunction "1_A1") (pintype "passive"))
      (node (ref "CLOCK") (pin "1") (pinfunction "VIN_1") (pintype "bidirectional"))
      (node (ref "CLOCK_CIN") (pin "1") (pinfunction "1_1") (pintype "passive"))
      (node (ref "COUT") (pin "1") (pinfunction "1_1") (pintype "passive"))
      (node (ref "C_BOOST_1") (pin "2") (pinfunction "2_2") (pintype "passive"))
      (node (ref "H1") (pin "7") (pinfunction "7_7") (pintype "passive"))
      (node (ref "H3") (pin "4") (pinfunction "4_4") (pintype "passive"))
      (node (ref "IC1") (pin "6") (pinfunction "SEN_6") (pintype "input"))
      (node (ref "ISP") (pin "2") (pinfunction "VCC_2") (pintype "power_in"))
      (node (ref "J1") (pin "PWR") (pinfunction "PWR_PWR") (pintype "bidirectional"))
      (node (ref "LD0_SD") (pin "1") (pinfunction "VIN_1") (pintype "bidirectional"))
      (node (ref "L_LPF") (pin "1") (pinfunction "1_1") (pintype "passive"))
      (node (ref "MCU") (pin "4") (pinfunction "VCC_4") (pintype "bidirectional"))
      (node (ref "MCU") (pin "6") (pinfunction "VCC_6") (pintype "bidirectional"))
      (node (ref "Q1") (pin "2") (pinfunction "S_2") (pintype "passive"))
      (node (ref "Q2") (pin "2") (pinfunction "S_2") (pintype "passive"))
      (node (ref "RCKL1") (pin "2") (pinfunction "2_2") (pintype "passive"))
      (node (ref "RN2") (pin "1") (pinfunction "1_1") (pintype "passive"))
      (node (ref "RN2") (pin "2") (pinfunction "1_2") (pintype "passive"))
      (node (ref "RSTAT") (pin "2") (pinfunction "2_2") (pintype "passive"))
      (node (ref "R_RESET") (pin "2") (pinfunction "2_2") (pintype "passive"))
      (node (ref "SD_CIN") (pin "1") (pinfunction "1_1") (pintype "passive"))
      (node (ref "SENSE_CIN") (pin "1") (pinfunction "1_1") (pintype "passive"))
    )
    (net (code "60") (name "VDD") (class "Default")
      (node (ref "C14") (pin "B1") (pinfunction "1_B1") (pintype "passive"))
      (node (ref "C_LDO_SD") (pin "2") (pinfunction "2_2") (pintype "passive"))
      (node (ref "LD0_SD") (pin "5") (pinfunction "VOUT_5") (pintype "bidirectional"))
      (node (ref "LSHIFT") (pin "1") (pinfunction "VDD_1") (pintype "power_in"))
      (node (ref "Q3") (pin "1") (pinfunction "G_1") (pintype "passive"))
      (node (ref "Q4") (pin "1") (pinfunction "G_1") (pintype "passive"))
      (node (ref "SD") (pin "4") (pinfunction "VDD_4") (pintype "power_in"))
    )
    (net (code "61") (name "VUSB") (class "Default")
      (node (ref "C17") (pin "1") (pinfunction "1_1") (pintype "passive"))
      (node (ref "C21") (pin "A") (pinfunction "+_A") (pintype "passive"))
      (node (ref "JP5") (pin "VBUS") (pinfunction "VBUS_VBUS") (pintype "bidirectional"))
      (node (ref "Q2") (pin "3") (pinfunction "D_3") (pintype "passive"))
      (node (ref "RN1") (pin "5") (pinfunction "2_5") (pintype "passive"))
      (node (ref "RN1") (pin "6") (pinfunction "2_6") (pintype "passive"))
      (node (ref "U2") (pin "12") (pinfunction "VCC_12") (pintype "bidirectional"))
    )
    (net (code "62") (name "unconnected-(3.3_SENSE-DNC-Pad8)") (class "Default")
      (node (ref "3.3_SENSE") (pin "8") (pinfunction "DNC_8") (pintype "no_connect"))
    )
    (net (code "63") (name "unconnected-(3.3_SENSE-DNC_2-Pad1)") (class "Default")
      (node (ref "3.3_SENSE") (pin "1") (pinfunction "DNC_2_1") (pintype "no_connect"))
    )
    (net (code "64") (name "unconnected-(3.3_SENSE-DNC_3-Pad5)") (class "Default")
      (node (ref "3.3_SENSE") (pin "5") (pinfunction "DNC_3_5") (pintype "no_connect"))
    )
    (net (code "65") (name "unconnected-(3.3_SENSE-DNC_4-Pad7)") (class "Default")
      (node (ref "3.3_SENSE") (pin "7") (pinfunction "DNC_4_7") (pintype "no_connect"))
    )
    (net (code "66") (name "unconnected-(CLOCK-BYP-Pad4)") (class "Default")
      (node (ref "CLOCK") (pin "4") (pinfunction "BYP_4") (pintype "bidirectional"))
    )
    (net (code "67") (name "unconnected-(LD0_SD-BYP-Pad4)") (class "Default")
      (node (ref "LD0_SD") (pin "4") (pinfunction "BYP_4") (pintype "bidirectional"))
    )
    (net (code "68") (name "unconnected-(LSHIFTD-O-Pad10)") (class "Default")
      (node (ref "LSHIFT") (pin "10") (pinfunction "O_10") (pintype "output"))
    )
    (net (code "69") (name "unconnected-(LSHIFTE-O-Pad12)") (class "Default")
      (node (ref "LSHIFT") (pin "12") (pinfunction "O_12") (pintype "output"))
    )
    (net (code "70") (name "unconnected-(LSHIFTF-O-Pad15)") (class "Default")
      (node (ref "LSHIFT") (pin "15") (pinfunction "O_15") (pintype "output"))
    )
    (net (code "71") (name "unconnected-(RTC-32KHZ-Pad1)") (class "Default")
      (node (ref "RTC") (pin "1") (pinfunction "32KHZ_1") (pintype "bidirectional"))
    )
    (net (code "72") (name "unconnected-(RTC-~{RST}-Pad4)") (class "Default")
      (node (ref "RTC") (pin "4") (pinfunction "~{RST}_4") (pintype "bidirectional"))
    )
    (net (code "73") (name "unconnected-(SD-CARD_DETECT-PadCD)") (class "Default")
      (node (ref "SD") (pin "CD") (pinfunction "CARD_DETECT_CD") (pintype "passive"))
    )
    (net (code "74") (name "unconnected-(SD-DAT1-Pad8)") (class "Default")
      (node (ref "SD") (pin "8") (pinfunction "DAT1_8") (pintype "bidirectional"))
    )
    (net (code "75") (name "unconnected-(SD-DAT2-Pad9)") (class "Default")
      (node (ref "SD") (pin "9") (pinfunction "DAT2_9") (pintype "bidirectional"))
    )
    (net (code "76") (name "unconnected-(SD-WRITE_PROTECT-PadWP)") (class "Default")
      (node (ref "SD") (pin "WP") (pinfunction "WRITE_PROTECT_WP") (pintype "passive"))
    )
    (net (code "77") (name "unconnected-(U2-CBUS0-Pad15)") (class "Default")
      (node (ref "U2") (pin "15") (pinfunction "CBUS0_15") (pintype "bidirectional"))
    )
    (net (code "78") (name "unconnected-(U2-CBUS3-Pad16)") (class "Default")
      (node (ref "U2") (pin "16") (pinfunction "CBUS3_16") (pintype "bidirectional"))
    )
    (net (code "79") (name "unconnected-(U2-DCD#-Pad5)") (class "Default")
      (node (ref "U2") (pin "5") (pinfunction "DCD#_5") (pintype "bidirectional"))
    )
    (net (code "80") (name "unconnected-(U2-DSR#-Pad4)") (class "Default")
      (node (ref "U2") (pin "4") (pinfunction "DSR#_4") (pintype "bidirectional"))
    )
    (net (code "81") (name "unconnected-(U2-RI#-Pad2)") (class "Default")
      (node (ref "U2") (pin "2") (pinfunction "RI#_2") (pintype "bidirectional"))
    )
    (net (code "82") (name "unconnected-(U2-RTS#-Pad19)") (class "Default")
      (node (ref "U2") (pin "19") (pinfunction "RTS#_19") (pintype "bidirectional"))
    )
  )
)
